# W5500_1.net
KiCad netlist of a schematic drawn in Altium Designer
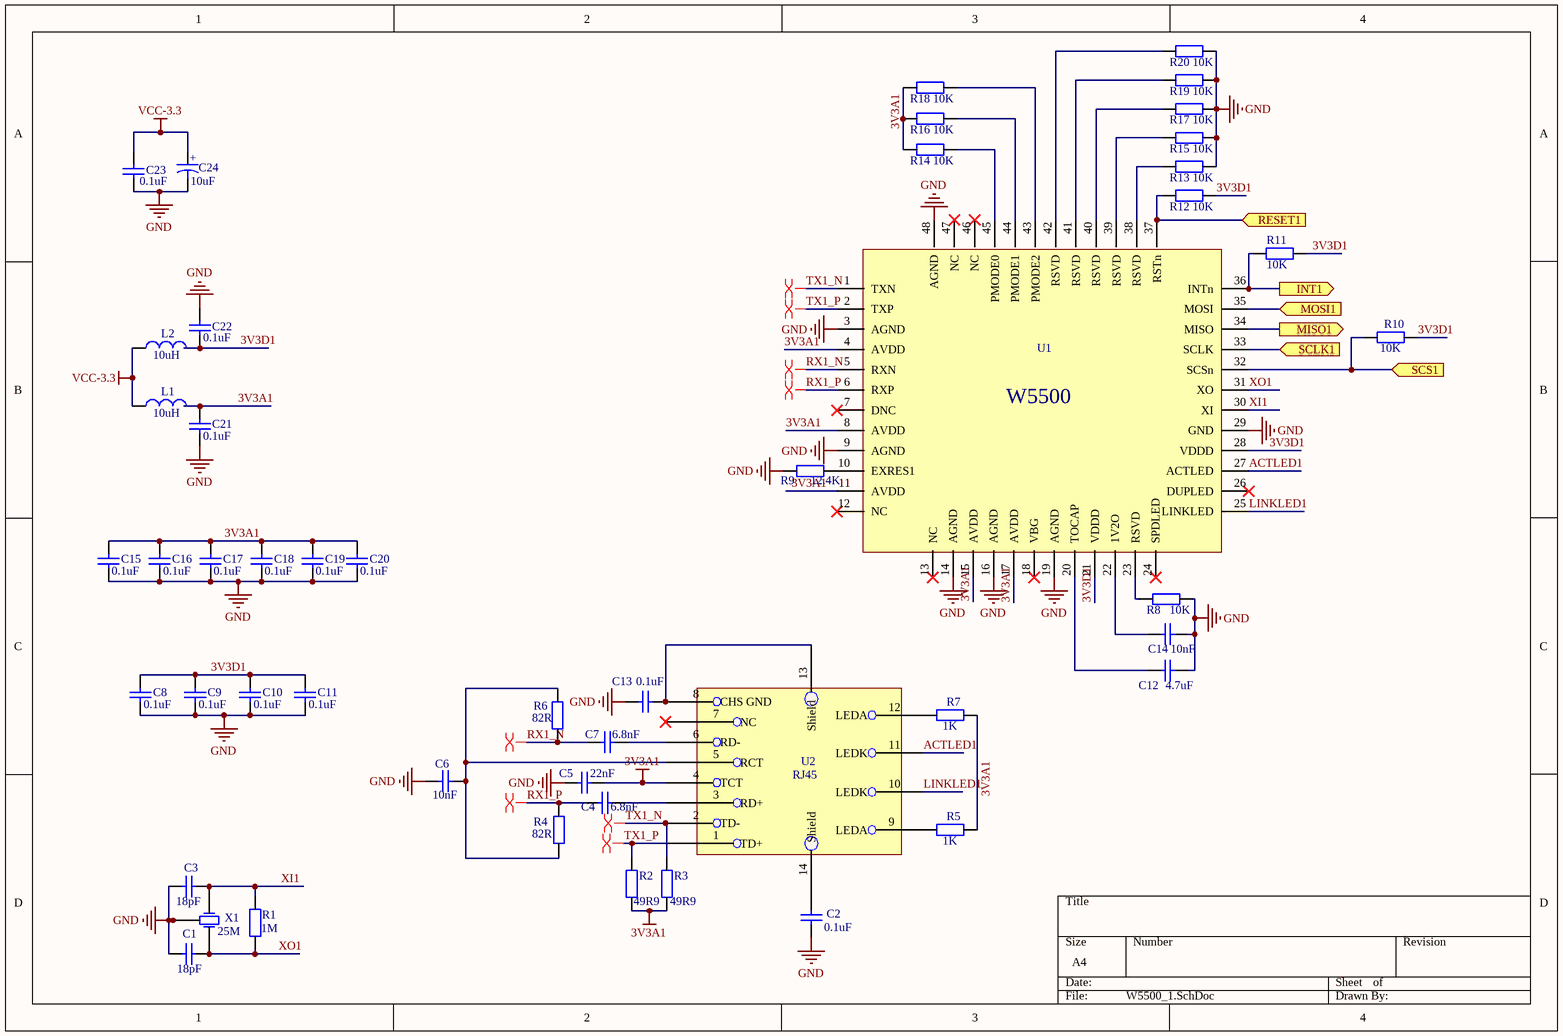
[diagram p0: W5500_1.SchDoc]

(export (version "E")
  (design (tool "Eeschema 10.0.6"))
  (components
    (comp (ref "C1")
      (value "18pF")
      (footprint "0603")
      (fields (field (name "Comment") "Capacitor-0603"))
      (libsource (lib "原理图库") (part "Capacitor-0603"))
    )
    (comp (ref "C2")
      (value "0.1uF")
      (footprint "0603")
      (fields (field (name "Comment") "Capacitor-0603"))
      (libsource (lib "原理图库") (part "Capacitor-0603"))
    )
    (comp (ref "C3")
      (value "18pF")
      (footprint "0603")
      (fields (field (name "Comment") "Capacitor-0603"))
      (libsource (lib "原理图库") (part "Capacitor-0603"))
    )
    (comp (ref "C4")
      (value "6.8nF")
      (footprint "0603")
      (fields (field (name "Comment") "Capacitor-0603"))
      (libsource (lib "原理图库") (part "Capacitor-0603"))
    )
    (comp (ref "C5")
      (value "22nF")
      (footprint "0603")
      (fields (field (name "Comment") "Capacitor-0603"))
      (libsource (lib "原理图库") (part "Capacitor-0603"))
    )
    (comp (ref "C6")
      (value "10nF")
      (footprint "0603")
      (fields (field (name "Comment") "Capacitor-0603"))
      (libsource (lib "原理图库") (part "Capacitor-0603"))
    )
    (comp (ref "C7")
      (value "6.8nF")
      (footprint "0603")
      (fields (field (name "Comment") "Capacitor-0603"))
      (libsource (lib "原理图库") (part "Capacitor-0603"))
    )
    (comp (ref "C8")
      (value "0.1uF")
      (footprint "0603")
      (fields (field (name "Comment") "Capacitor-0603"))
      (libsource (lib "原理图库") (part "Capacitor-0603"))
    )
    (comp (ref "C9")
      (value "0.1uF")
      (footprint "0603")
      (fields (field (name "Comment") "Capacitor-0603"))
      (libsource (lib "原理图库") (part "Capacitor-0603"))
    )
    (comp (ref "C10")
      (value "0.1uF")
      (footprint "0603")
      (fields (field (name "Comment") "Capacitor-0603"))
      (libsource (lib "原理图库") (part "Capacitor-0603"))
    )
    (comp (ref "C11")
      (value "0.1uF")
      (footprint "0603")
      (fields (field (name "Comment") "Capacitor-0603"))
      (libsource (lib "原理图库") (part "Capacitor-0603"))
    )
    (comp (ref "C12")
      (value "4.7uF")
      (footprint "0603")
      (fields (field (name "Comment") "Capacitor-0805"))
      (libsource (lib "原理图库") (part "Capacitor-0805"))
    )
    (comp (ref "C13")
      (value "0.1uF")
      (footprint "0603")
      (fields (field (name "Comment") "Capacitor-0603"))
      (libsource (lib "原理图库") (part "Capacitor-0603"))
    )
    (comp (ref "C14")
      (value "10nF")
      (footprint "0603")
      (fields (field (name "Comment") "Capacitor-0603"))
      (libsource (lib "原理图库") (part "Capacitor-0603"))
    )
    (comp (ref "C15")
      (value "0.1uF")
      (footprint "0603")
      (fields (field (name "Comment") "Capacitor-0603"))
      (libsource (lib "原理图库") (part "Capacitor-0603"))
    )
    (comp (ref "C16")
      (value "0.1uF")
      (footprint "0603")
      (fields (field (name "Comment") "Capacitor-0603"))
      (libsource (lib "原理图库") (part "Capacitor-0603"))
    )
    (comp (ref "C17")
      (value "0.1uF")
      (footprint "0603")
      (fields (field (name "Comment") "Capacitor-0603"))
      (libsource (lib "原理图库") (part "Capacitor-0603"))
    )
    (comp (ref "C18")
      (value "0.1uF")
      (footprint "0603")
      (fields (field (name "Comment") "Capacitor-0603"))
      (libsource (lib "原理图库") (part "Capacitor-0603"))
    )
    (comp (ref "C19")
      (value "0.1uF")
      (footprint "0603")
      (fields (field (name "Comment") "Capacitor-0603"))
      (libsource (lib "原理图库") (part "Capacitor-0603"))
    )
    (comp (ref "C20")
      (value "0.1uF")
      (footprint "0603")
      (fields (field (name "Comment") "Capacitor-0603"))
      (libsource (lib "原理图库") (part "Capacitor-0603"))
    )
    (comp (ref "C21")
      (value "0.1uF")
      (footprint "0603")
      (fields (field (name "Comment") "Capacitor-0603"))
      (libsource (lib "原理图库") (part "Capacitor-0603"))
    )
    (comp (ref "C22")
      (value "0.1uF")
      (footprint "0603")
      (fields (field (name "Comment") "Capacitor-0603"))
      (libsource (lib "原理图库") (part "Capacitor-0603"))
    )
    (comp (ref "C23")
      (value "0.1uF")
      (footprint "0603")
      (fields (field (name "Comment") "Capacitor-0603"))
      (libsource (lib "原理图库") (part "Capacitor-0603"))
    )
    (comp (ref "C24")
      (value "10uF")
      (footprint "钽电容1206（A3216）")
      (fields (field (name "ALTIUM_UNNAMED_1") "+") (field (name "Comment") "电解电容"))
      (libsource (lib "原理图库") (part "电解电容"))
    )
    (comp (ref "L1")
      (value "10uH")
      (footprint "0805")
      (fields (field (name "Comment") "Inductor"))
      (libsource (lib "原理图库") (part "Inductor"))
    )
    (comp (ref "L2")
      (value "10uH")
      (footprint "0805")
      (fields (field (name "Comment") "Inductor"))
      (libsource (lib "原理图库") (part "Inductor"))
    )
    (comp (ref "R1")
      (value "1M")
      (footprint "0603")
      (fields (field (name "Comment") "Resistor-0603"))
      (libsource (lib "") (part "Resistor-0603_1"))
    )
    (comp (ref "R2")
      (value "49R9")
      (footprint "0603")
      (fields (field (name "Comment") "Resistor-0603"))
      (libsource (lib "") (part "Resistor-0603_1"))
    )
    (comp (ref "R3")
      (value "49R9")
      (footprint "0603")
      (fields (field (name "Comment") "Resistor-0603"))
      (libsource (lib "") (part "Resistor-0603_1"))
    )
    (comp (ref "R4")
      (value "82R")
      (footprint "0603")
      (fields (field (name "Comment") "Resistor-0603"))
      (libsource (lib "") (part "Resistor-0603_1"))
    )
    (comp (ref "R5")
      (value "1K")
      (footprint "0603")
      (fields (field (name "Comment") "Resistor-0603"))
      (libsource (lib "原理图库") (part "Resistor-0603"))
    )
    (comp (ref "R6")
      (value "82R")
      (footprint "0603")
      (fields (field (name "Comment") "Resistor-0603"))
      (libsource (lib "") (part "Resistor-0603_1"))
    )
    (comp (ref "R7")
      (value "1K")
      (footprint "0603")
      (fields (field (name "Comment") "Resistor-0603"))
      (libsource (lib "原理图库") (part "Resistor-0603"))
    )
    (comp (ref "R8")
      (value "10K")
      (footprint "0603")
      (fields (field (name "Comment") "Resistor-0603"))
      (libsource (lib "") (part "Resistor-0603_2"))
    )
    (comp (ref "R9")
      (value "12.4K")
      (footprint "0603")
      (fields (field (name "Comment") "Resistor-0603"))
      (libsource (lib "") (part "Resistor-0603_2"))
    )
    (comp (ref "R10")
      (value "10K")
      (footprint "0603")
      (fields (field (name "Comment") "Resistor-0603"))
      (libsource (lib "原理图库") (part "Resistor-0603"))
    )
    (comp (ref "R11")
      (value "10K")
      (footprint "0603")
      (fields (field (name "Comment") "Resistor-0603"))
      (libsource (lib "原理图库") (part "Resistor-0603"))
    )
    (comp (ref "R12")
      (value "10K")
      (footprint "0603")
      (fields (field (name "Comment") "Resistor-0603"))
      (libsource (lib "") (part "Resistor-0603_2"))
    )
    (comp (ref "R13")
      (value "10K")
      (footprint "0603")
      (fields (field (name "Comment") "Resistor-0603"))
      (libsource (lib "") (part "Resistor-0603_2"))
    )
    (comp (ref "R14")
      (value "10K")
      (footprint "0603")
      (fields (field (name "Comment") "Resistor-0603"))
      (libsource (lib "") (part "Resistor-0603_2"))
    )
    (comp (ref "R15")
      (value "10K")
      (footprint "0603")
      (fields (field (name "Comment") "Resistor-0603"))
      (libsource (lib "") (part "Resistor-0603_2"))
    )
    (comp (ref "R16")
      (value "10K")
      (footprint "0603")
      (fields (field (name "Comment") "Resistor-0603"))
      (libsource (lib "") (part "Resistor-0603_2"))
    )
    (comp (ref "R17")
      (value "10K")
      (footprint "0603")
      (fields (field (name "Comment") "Resistor-0603"))
      (libsource (lib "") (part "Resistor-0603_2"))
    )
    (comp (ref "R18")
      (value "10K")
      (footprint "0603")
      (fields (field (name "Comment") "Resistor-0603"))
      (libsource (lib "") (part "Resistor-0603_2"))
    )
    (comp (ref "R19")
      (value "10K")
      (footprint "0603")
      (fields (field (name "Comment") "Resistor-0603"))
      (libsource (lib "") (part "Resistor-0603_2"))
    )
    (comp (ref "R20")
      (value "10K")
      (footprint "0603")
      (fields (field (name "Comment") "Resistor-0603"))
      (libsource (lib "") (part "Resistor-0603_2"))
    )
    (comp (ref "U1") (value "W5500") (footprint "W5500") (libsource (lib "原理图库") (part "W5500")))
    (comp (ref "U2")
      (value "RJ45")
      (footprint "RJ45")
      (fields (field (name "NAME") "RJ45"))
      (libsource (lib "原理图库") (part "RJ45"))
    )
    (comp (ref "X1")
      (value "25M")
      (footprint "3225无源晶振")
      (fields (field (name "Comment") "3225无源晶振"))
      (libsource (lib "原理图库") (part "3225无源晶振"))
    )
  )
  (nets
    (net (code "1") (name "/3V3D1") (class "Default")
      (node (ref "C10") (pin "1") (pinfunction "1_1") (pintype "passive"))
      (node (ref "C11") (pin "1") (pinfunction "1_1") (pintype "passive"))
      (node (ref "C22") (pin "1") (pinfunction "1_1") (pintype "passive"))
      (node (ref "C8") (pin "1") (pinfunction "1_1") (pintype "passive"))
      (node (ref "C9") (pin "1") (pinfunction "1_1") (pintype "passive"))
      (node (ref "L2") (pin "2") (pinfunction "2_2") (pintype "passive"))
      (node (ref "R10") (pin "2") (pinfunction "2_2") (pintype "passive"))
      (node (ref "R11") (pin "2") (pinfunction "2_2") (pintype "passive"))
      (node (ref "R12") (pin "1") (pinfunction "1_1") (pintype "passive"))
      (node (ref "U1") (pin "21") (pinfunction "VDDD_21") (pintype "passive"))
      (node (ref "U1") (pin "28") (pinfunction "VDDD_28") (pintype "passive"))
    )
    (net (code "2") (name "/ACTLED1") (class "Default")
      (node (ref "U1") (pin "27") (pinfunction "ACTLED_27") (pintype "passive"))
      (node (ref "U2") (pin "11") (pinfunction "LEDK_11") (pintype "passive"))
    )
    (net (code "3") (name "/INT1") (class "Default")
      (node (ref "R11") (pin "1") (pinfunction "1_1") (pintype "passive"))
      (node (ref "U1") (pin "36") (pinfunction "INTn_36") (pintype "passive"))
    )
    (net (code "4") (name "/LINKLED1") (class "Default")
      (node (ref "U1") (pin "25") (pinfunction "LINKLED_25") (pintype "passive"))
      (node (ref "U2") (pin "10") (pinfunction "LEDK_10") (pintype "passive"))
    )
    (net (code "5") (name "/MISO1") (class "Default")
      (node (ref "U1") (pin "34") (pinfunction "MISO_34") (pintype "passive"))
    )
    (net (code "6") (name "/MOSI1") (class "Default")
      (node (ref "U1") (pin "35") (pinfunction "MOSI_35") (pintype "passive"))
    )
    (net (code "7") (name "/RESET1") (class "Default")
      (node (ref "R12") (pin "2") (pinfunction "2_2") (pintype "passive"))
      (node (ref "U1") (pin "37") (pinfunction "RSTn_37") (pintype "passive"))
    )
    (net (code "8") (name "/RX1_N") (class "Default")
      (node (ref "C7") (pin "1") (pinfunction "1_1") (pintype "passive"))
      (node (ref "R6") (pin "2") (pinfunction "2_2") (pintype "passive"))
      (node (ref "U1") (pin "5") (pinfunction "RXN_5") (pintype "passive"))
    )
    (net (code "9") (name "/RX1_P") (class "Default")
      (node (ref "C4") (pin "1") (pinfunction "1_1") (pintype "passive"))
      (node (ref "R4") (pin "1") (pinfunction "1_1") (pintype "passive"))
      (node (ref "U1") (pin "6") (pinfunction "RXP_6") (pintype "passive"))
    )
    (net (code "10") (name "/SCLK1") (class "Default")
      (node (ref "U1") (pin "33") (pinfunction "SCLK_33") (pintype "passive"))
    )
    (net (code "11") (name "/SCS1") (class "Default")
      (node (ref "R10") (pin "1") (pinfunction "1_1") (pintype "passive"))
      (node (ref "U1") (pin "32") (pinfunction "SCSn_32") (pintype "passive"))
    )
    (net (code "12") (name "/TX1_N") (class "Default")
      (node (ref "R3") (pin "1") (pinfunction "1_1") (pintype "passive"))
      (node (ref "U1") (pin "1") (pinfunction "TXN_1") (pintype "passive"))
      (node (ref "U2") (pin "2") (pinfunction "TD-_2") (pintype "passive"))
    )
    (net (code "13") (name "/TX1_P") (class "Default")
      (node (ref "R2") (pin "1") (pinfunction "1_1") (pintype "passive"))
      (node (ref "U1") (pin "2") (pinfunction "TXP_2") (pintype "passive"))
      (node (ref "U2") (pin "1") (pinfunction "TD+_1") (pintype "passive"))
    )
    (net (code "14") (name "/XI1") (class "Default")
      (node (ref "C3") (pin "2") (pinfunction "2_2") (pintype "passive"))
      (node (ref "R1") (pin "1") (pinfunction "1_1") (pintype "passive"))
      (node (ref "U1") (pin "30") (pinfunction "XI_30") (pintype "passive"))
      (node (ref "X1") (pin "1") (pinfunction "OSC1_1") (pintype "passive"))
    )
    (net (code "15") (name "/XO1") (class "Default")
      (node (ref "C1") (pin "2") (pinfunction "2_2") (pintype "passive"))
      (node (ref "R1") (pin "2") (pinfunction "2_2") (pintype "passive"))
      (node (ref "U1") (pin "31") (pinfunction "XO_31") (pintype "passive"))
      (node (ref "X1") (pin "3") (pinfunction "OSC2_3") (pintype "passive"))
    )
    (net (code "16") (name "3V3A1") (class "Default")
      (node (ref "C15") (pin "1") (pinfunction "1_1") (pintype "passive"))
      (node (ref "C16") (pin "1") (pinfunction "1_1") (pintype "passive"))
      (node (ref "C17") (pin "1") (pinfunction "1_1") (pintype "passive"))
      (node (ref "C18") (pin "1") (pinfunction "1_1") (pintype "passive"))
      (node (ref "C19") (pin "1") (pinfunction "1_1") (pintype "passive"))
      (node (ref "C20") (pin "1") (pinfunction "1_1") (pintype "passive"))
      (node (ref "C21") (pin "1") (pinfunction "1_1") (pintype "passive"))
      (node (ref "C5") (pin "2") (pinfunction "2_2") (pintype "passive"))
      (node (ref "L1") (pin "2") (pinfunction "2_2") (pintype "passive"))
      (node (ref "R14") (pin "2") (pinfunction "2_2") (pintype "passive"))
      (node (ref "R16") (pin "2") (pinfunction "2_2") (pintype "passive"))
      (node (ref "R18") (pin "2") (pinfunction "2_2") (pintype "passive"))
      (node (ref "R2") (pin "2") (pinfunction "2_2") (pintype "passive"))
      (node (ref "R3") (pin "2") (pinfunction "2_2") (pintype "passive"))
      (node (ref "R5") (pin "2") (pinfunction "2_2") (pintype "passive"))
      (node (ref "R7") (pin "2") (pinfunction "2_2") (pintype "passive"))
      (node (ref "U1") (pin "11") (pinfunction "AVDD_11") (pintype "passive"))
      (node (ref "U1") (pin "15") (pinfunction "AVDD_15") (pintype "passive"))
      (node (ref "U1") (pin "17") (pinfunction "AVDD_17") (pintype "passive"))
      (node (ref "U1") (pin "4") (pinfunction "AVDD_4") (pintype "passive"))
      (node (ref "U1") (pin "8") (pinfunction "AVDD_8") (pintype "passive"))
      (node (ref "U2") (pin "4") (pinfunction "TCT_4") (pintype "passive"))
    )
    (net (code "17") (name "GND") (class "Default")
      (node (ref "C1") (pin "1") (pinfunction "1_1") (pintype "passive"))
      (node (ref "C10") (pin "2") (pinfunction "2_2") (pintype "passive"))
      (node (ref "C11") (pin "2") (pinfunction "2_2") (pintype "passive"))
      (node (ref "C12") (pin "2") (pinfunction "2_2") (pintype "passive"))
      (node (ref "C13") (pin "2") (pinfunction "2_2") (pintype "passive"))
      (node (ref "C14") (pin "1") (pinfunction "1_1") (pintype "passive"))
      (node (ref "C15") (pin "2") (pinfunction "2_2") (pintype "passive"))
      (node (ref "C16") (pin "2") (pinfunction "2_2") (pintype "passive"))
      (node (ref "C17") (pin "2") (pinfunction "2_2") (pintype "passive"))
      (node (ref "C18") (pin "2") (pinfunction "2_2") (pintype "passive"))
      (node (ref "C19") (pin "2") (pinfunction "2_2") (pintype "passive"))
      (node (ref "C2") (pin "2") (pinfunction "2_2") (pintype "passive"))
      (node (ref "C20") (pin "2") (pinfunction "2_2") (pintype "passive"))
      (node (ref "C21") (pin "2") (pinfunction "2_2") (pintype "passive"))
      (node (ref "C22") (pin "2") (pinfunction "2_2") (pintype "passive"))
      (node (ref "C23") (pin "1") (pinfunction "1_1") (pintype "passive"))
      (node (ref "C24") (pin "1") (pinfunction "1_1") (pintype "passive"))
      (node (ref "C3") (pin "1") (pinfunction "1_1") (pintype "passive"))
      (node (ref "C5") (pin "1") (pinfunction "1_1") (pintype "passive"))
      (node (ref "C6") (pin "1") (pinfunction "1_1") (pintype "passive"))
      (node (ref "C8") (pin "2") (pinfunction "2_2") (pintype "passive"))
      (node (ref "C9") (pin "2") (pinfunction "2_2") (pintype "passive"))
      (node (ref "R13") (pin "1") (pinfunction "1_1") (pintype "passive"))
      (node (ref "R15") (pin "1") (pinfunction "1_1") (pintype "passive"))
      (node (ref "R17") (pin "1") (pinfunction "1_1") (pintype "passive"))
      (node (ref "R19") (pin "1") (pinfunction "1_1") (pintype "passive"))
      (node (ref "R20") (pin "1") (pinfunction "1_1") (pintype "passive"))
      (node (ref "R8") (pin "1") (pinfunction "1_1") (pintype "passive"))
      (node (ref "R9") (pin "2") (pinfunction "2_2") (pintype "passive"))
      (node (ref "U1") (pin "14") (pinfunction "AGND_14") (pintype "passive"))
      (node (ref "U1") (pin "16") (pinfunction "AGND_16") (pintype "passive"))
      (node (ref "U1") (pin "19") (pinfunction "AGND_19") (pintype "passive"))
      (node (ref "U1") (pin "29") (pinfunction "GND_29") (pintype "passive"))
      (node (ref "U1") (pin "3") (pinfunction "AGND_3") (pintype "passive"))
      (node (ref "U1") (pin "48") (pinfunction "AGND_48") (pintype "passive"))
      (node (ref "U1") (pin "9") (pinfunction "AGND_9") (pintype "passive"))
      (node (ref "X1") (pin "2") (pinfunction "GND_2") (pintype "passive"))
      (node (ref "X1") (pin "4") (pinfunction "GND_4") (pintype "passive"))
    )
    (net (code "18") (name "Net-(C2-Pad1)") (class "Default")
      (node (ref "C2") (pin "1") (pinfunction "1_1") (pintype "passive"))
      (node (ref "U2") (pin "14") (pinfunction "Shield_14") (pintype "passive"))
    )
    (net (code "19") (name "Net-(R5-Pad1)") (class "Default")
      (node (ref "R5") (pin "1") (pinfunction "1_1") (pintype "passive"))
      (node (ref "U2") (pin "9") (pinfunction "LEDA_9") (pintype "passive"))
    )
    (net (code "20") (name "Net-(R7-Pad1)") (class "Default")
      (node (ref "R7") (pin "1") (pinfunction "1_1") (pintype "passive"))
      (node (ref "U2") (pin "12") (pinfunction "LEDA_12") (pintype "passive"))
    )
    (net (code "21") (name "Net-(R8-Pad2)") (class "Default")
      (node (ref "R8") (pin "2") (pinfunction "2_2") (pintype "passive"))
      (node (ref "U1") (pin "23") (pinfunction "RSVD_23") (pintype "passive"))
    )
    (net (code "22") (name "Net-(R13-Pad2)") (class "Default")
      (node (ref "R13") (pin "2") (pinfunction "2_2") (pintype "passive"))
      (node (ref "U1") (pin "38") (pinfunction "RSVD_38") (pintype "passive"))
    )
    (net (code "23") (name "Net-(R15-Pad2)") (class "Default")
      (node (ref "R15") (pin "2") (pinfunction "2_2") (pintype "passive"))
      (node (ref "U1") (pin "39") (pinfunction "RSVD_39") (pintype "passive"))
    )
    (net (code "24") (name "Net-(R17-Pad2)") (class "Default")
      (node (ref "R17") (pin "2") (pinfunction "2_2") (pintype "passive"))
      (node (ref "U1") (pin "40") (pinfunction "RSVD_40") (pintype "passive"))
    )
    (net (code "25") (name "Net-(R19-Pad2)") (class "Default")
      (node (ref "R19") (pin "2") (pinfunction "2_2") (pintype "passive"))
      (node (ref "U1") (pin "41") (pinfunction "RSVD_41") (pintype "passive"))
    )
    (net (code "26") (name "Net-(R20-Pad2)") (class "Default")
      (node (ref "R20") (pin "2") (pinfunction "2_2") (pintype "passive"))
      (node (ref "U1") (pin "42") (pinfunction "RSVD_42") (pintype "passive"))
    )
    (net (code "27") (name "Net-(U1-1V2O)") (class "Default")
      (node (ref "C14") (pin "2") (pinfunction "2_2") (pintype "passive"))
      (node (ref "U1") (pin "22") (pinfunction "1V2O_22") (pintype "passive"))
    )
    (net (code "28") (name "Net-(U1-EXRES1)") (class "Default")
      (node (ref "R9") (pin "1") (pinfunction "1_1") (pintype "passive"))
      (node (ref "U1") (pin "10") (pinfunction "EXRES1_10") (pintype "passive"))
    )
    (net (code "29") (name "Net-(U1-PMODE0)") (class "Default")
      (node (ref "R14") (pin "1") (pinfunction "1_1") (pintype "passive"))
      (node (ref "U1") (pin "45") (pinfunction "PMODE0_45") (pintype "passive"))
    )
    (net (code "30") (name "Net-(U1-PMODE1)") (class "Default")
      (node (ref "R16") (pin "1") (pinfunction "1_1") (pintype "passive"))
      (node (ref "U1") (pin "44") (pinfunction "PMODE1_44") (pintype "passive"))
    )
    (net (code "31") (name "Net-(U1-PMODE2)") (class "Default")
      (node (ref "R18") (pin "1") (pinfunction "1_1") (pintype "passive"))
      (node (ref "U1") (pin "43") (pinfunction "PMODE2_43") (pintype "passive"))
    )
    (net (code "32") (name "Net-(U1-TOCAP)") (class "Default")
      (node (ref "C12") (pin "1") (pinfunction "1_1") (pintype "passive"))
      (node (ref "U1") (pin "20") (pinfunction "TOCAP_20") (pintype "passive"))
    )
    (net (code "33") (name "Net-(U2-CHS_GND)") (class "Default")
      (node (ref "C13") (pin "1") (pinfunction "1_1") (pintype "passive"))
      (node (ref "U2") (pin "13") (pinfunction "Shield_13") (pintype "passive"))
      (node (ref "U2") (pin "8") (pinfunction "CHS_GND_8") (pintype "passive"))
    )
    (net (code "34") (name "Net-(U2-RCT)") (class "Default")
      (node (ref "C6") (pin "2") (pinfunction "2_2") (pintype "passive"))
      (node (ref "R4") (pin "2") (pinfunction "2_2") (pintype "passive"))
      (node (ref "R6") (pin "1") (pinfunction "1_1") (pintype "passive"))
      (node (ref "U2") (pin "5") (pinfunction "RCT_5") (pintype "passive"))
    )
    (net (code "35") (name "Net-(U2-RD+)") (class "Default")
      (node (ref "C4") (pin "2") (pinfunction "2_2") (pintype "passive"))
      (node (ref "U2") (pin "3") (pinfunction "RD+_3") (pintype "passive"))
    )
    (net (code "36") (name "Net-(U2-RD-)") (class "Default")
      (node (ref "C7") (pin "2") (pinfunction "2_2") (pintype "passive"))
      (node (ref "U2") (pin "6") (pinfunction "RD-_6") (pintype "passive"))
    )
    (net (code "37") (name "VCC-3.3") (class "Default")
      (node (ref "C23") (pin "2") (pinfunction "2_2") (pintype "passive"))
      (node (ref "C24") (pin "2") (pinfunction "2_2") (pintype "passive"))
      (node (ref "L1") (pin "1") (pinfunction "1_1") (pintype "passive"))
      (node (ref "L2") (pin "1") (pinfunction "1_1") (pintype "passive"))
    )
    (net (code "38") (name "unconnected-(U1-DNC-Pad7)") (class "Default")
      (node (ref "U1") (pin "7") (pinfunction "DNC_7") (pintype "passive+no_connect"))
    )
    (net (code "39") (name "unconnected-(U1-DUPLED-Pad26)") (class "Default")
      (node (ref "U1") (pin "26") (pinfunction "DUPLED_26") (pintype "passive+no_connect"))
    )
    (net (code "40") (name "unconnected-(U1-NC-Pad12)") (class "Default")
      (node (ref "U1") (pin "12") (pinfunction "NC_12") (pintype "passive+no_connect"))
    )
    (net (code "41") (name "unconnected-(U1-NC-Pad13)") (class "Default")
      (node (ref "U1") (pin "13") (pinfunction "NC_13") (pintype "passive+no_connect"))
    )
    (net (code "42") (name "unconnected-(U1-NC-Pad46)") (class "Default")
      (node (ref "U1") (pin "46") (pinfunction "NC_46") (pintype "passive+no_connect"))
    )
    (net (code "43") (name "unconnected-(U1-NC-Pad47)") (class "Default")
      (node (ref "U1") (pin "47") (pinfunction "NC_47") (pintype "passive+no_connect"))
    )
    (net (code "44") (name "unconnected-(U1-SPDLED-Pad24)") (class "Default")
      (node (ref "U1") (pin "24") (pinfunction "SPDLED_24") (pintype "passive+no_connect"))
    )
    (net (code "45") (name "unconnected-(U1-VBG-Pad18)") (class "Default")
      (node (ref "U1") (pin "18") (pinfunction "VBG_18") (pintype "passive+no_connect"))
    )
    (net (code "46") (name "unconnected-(U2-NC-Pad7)") (class "Default")
      (node (ref "U2") (pin "7") (pinfunction "NC_7") (pintype "passive+no_connect"))
    )
  )
)
